# receiverNode_Uno.net
KiCad netlist of a schematic drawn in EAGLE
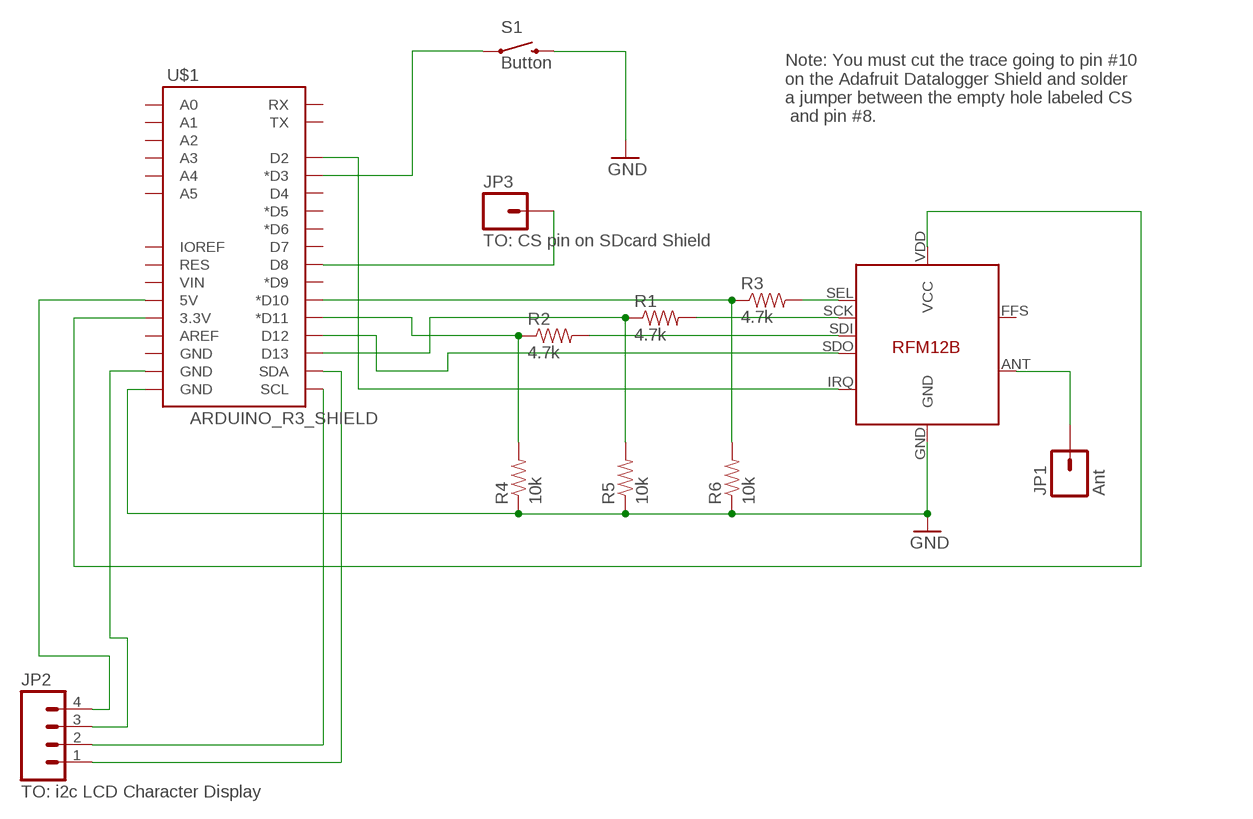
[diagram p0: schematic, sheet 1]

(export (version "E")
  (design (tool "Eeschema 10.0.6"))
  (components
    (comp (ref "JP1")
      (value "Ant")
      (footprint "eagle-import:1X01_LONGPAD")
      (libsource (lib "eagle-import") (part "M01PTH_LONGPAD"))
    )
    (comp (ref "JP2")
      (value "TO: i2c LCD Character Display")
      (footprint "eagle-import:1X04_LONGPADS")
      (libsource (lib "eagle-import") (part "M04LONGPADS"))
    )
    (comp (ref "JP3")
      (value "TO: CS pin on SDcard Shield")
      (footprint "eagle-import:1X01_LONGPAD")
      (libsource (lib "eagle-import") (part "M01PTH_LONGPAD"))
    )
    (comp (ref "R1")
      (value "4.7k")
      (footprint "eagle-import:AXIAL-0.3")
      (libsource (lib "eagle-import") (part "RESISTORAXIAL-0.3"))
    )
    (comp (ref "R2")
      (value "4.7k")
      (footprint "eagle-import:AXIAL-0.3")
      (libsource (lib "eagle-import") (part "RESISTORAXIAL-0.3"))
    )
    (comp (ref "R3")
      (value "4.7k")
      (footprint "eagle-import:AXIAL-0.3")
      (libsource (lib "eagle-import") (part "RESISTORAXIAL-0.3"))
    )
    (comp (ref "R4")
      (value "10k")
      (footprint "eagle-import:AXIAL-0.3")
      (libsource (lib "eagle-import") (part "RESISTORAXIAL-0.3"))
    )
    (comp (ref "R5")
      (value "10k")
      (footprint "eagle-import:AXIAL-0.3")
      (libsource (lib "eagle-import") (part "RESISTORAXIAL-0.3"))
    )
    (comp (ref "R6")
      (value "10k")
      (footprint "eagle-import:AXIAL-0.3")
      (libsource (lib "eagle-import") (part "RESISTORAXIAL-0.3"))
    )
    (comp (ref "S1")
      (value "Button")
      (footprint "eagle-import:TACTILE-PTH")
      (libsource (lib "eagle-import") (part "SWITCH-MOMENTARY-2PTH"))
    )
    (comp (ref "U$1")
      (value "ARDUINO_R3_SHIELD")
      (footprint "eagle-import:UNO_R3_SHIELD")
      (libsource (lib "eagle-import") (part "ARDUINO_R3_SHIELD"))
    )
    (comp (ref "U$2")
      (value "RFM12B")
      (footprint "eagle-import:RFM12B")
      (libsource (lib "eagle-import") (part "RFM12B"))
    )
  )
  (nets
    (net (code "1") (name "GND") (class "Default")
      (node (ref "R4") (pin "P$1") (pinfunction "1_P$1") (pintype "passive"))
      (node (ref "R5") (pin "P$1") (pinfunction "1_P$1") (pintype "passive"))
      (node (ref "R6") (pin "P$1") (pinfunction "1_P$1") (pintype "passive"))
      (node (ref "S1") (pin "3") (pinfunction "2_3") (pintype "passive"))
      (node (ref "U$1") (pin "GND@0") (pinfunction "GND_GND@0") (pintype "bidirectional"))
      (node (ref "U$2") (pin "GND") (pinfunction "GND_GND") (pintype "power_in"))
    )
    (net (code "2") (name "Net-(JP1-Pad1)") (class "Default")
      (node (ref "JP1") (pin "1") (pinfunction "1_1") (pintype "passive"))
      (node (ref "U$2") (pin "ANT") (pinfunction "ANT_ANT") (pintype "passive"))
    )
    (net (code "3") (name "Net-(JP2-Pad1)") (class "Default")
      (node (ref "JP2") (pin "1") (pinfunction "1_1") (pintype "passive"))
      (node (ref "U$1") (pin "SDA") (pinfunction "SDA_SDA") (pintype "bidirectional"))
    )
    (net (code "4") (name "Net-(JP2-Pad2)") (class "Default")
      (node (ref "JP2") (pin "2") (pinfunction "2_2") (pintype "passive"))
      (node (ref "U$1") (pin "SCL") (pinfunction "SCL_SCL") (pintype "bidirectional"))
    )
    (net (code "5") (name "Net-(JP2-Pad3)") (class "Default")
      (node (ref "JP2") (pin "3") (pinfunction "3_3") (pintype "passive"))
      (node (ref "U$1") (pin "GND@1") (pinfunction "GND_GND@1") (pintype "bidirectional"))
    )
    (net (code "6") (name "Net-(JP2-Pad4)") (class "Default")
      (node (ref "JP2") (pin "4") (pinfunction "4_4") (pintype "passive"))
      (node (ref "U$1") (pin "5V") (pinfunction "5V_5V") (pintype "bidirectional"))
    )
    (net (code "7") (name "Net-(JP3-Pad1)") (class "Default")
      (node (ref "JP3") (pin "1") (pinfunction "1_1") (pintype "passive"))
      (node (ref "U$1") (pin "D8") (pinfunction "D8_D8") (pintype "bidirectional"))
    )
    (net (code "8") (name "Net-(R1-1)") (class "Default")
      (node (ref "R1") (pin "P$1") (pinfunction "1_P$1") (pintype "passive"))
      (node (ref "R5") (pin "P$2") (pinfunction "2_P$2") (pintype "passive"))
      (node (ref "U$1") (pin "D13") (pinfunction "D13_D13") (pintype "bidirectional"))
    )
    (net (code "9") (name "Net-(R1-2)") (class "Default")
      (node (ref "R1") (pin "P$2") (pinfunction "2_P$2") (pintype "passive"))
      (node (ref "U$2") (pin "SCK") (pinfunction "SCK_SCK") (pintype "input"))
    )
    (net (code "10") (name "Net-(R2-1)") (class "Default")
      (node (ref "R2") (pin "P$1") (pinfunction "1_P$1") (pintype "passive"))
      (node (ref "R4") (pin "P$2") (pinfunction "2_P$2") (pintype "passive"))
      (node (ref "U$1") (pin "D11") (pinfunction "*D11_D11") (pintype "bidirectional"))
    )
    (net (code "11") (name "Net-(R2-2)") (class "Default")
      (node (ref "R2") (pin "P$2") (pinfunction "2_P$2") (pintype "passive"))
      (node (ref "U$2") (pin "SDI") (pinfunction "SDI_SDI") (pintype "input"))
    )
    (net (code "12") (name "Net-(R3-1)") (class "Default")
      (node (ref "R3") (pin "P$1") (pinfunction "1_P$1") (pintype "passive"))
      (node (ref "R6") (pin "P$2") (pinfunction "2_P$2") (pintype "passive"))
      (node (ref "U$1") (pin "D10") (pinfunction "*D10_D10") (pintype "bidirectional"))
    )
    (net (code "13") (name "Net-(R3-2)") (class "Default")
      (node (ref "R3") (pin "P$2") (pinfunction "2_P$2") (pintype "passive"))
      (node (ref "U$2") (pin "SEL") (pinfunction "SEL_SEL") (pintype "input"))
    )
    (net (code "14") (name "Net-(U$1-*D3)") (class "Default")
      (node (ref "S1") (pin "1") (pinfunction "1_1") (pintype "passive"))
      (node (ref "U$1") (pin "D3") (pinfunction "*D3_D3") (pintype "bidirectional"))
    )
    (net (code "15") (name "Net-(U$1-PadD2)") (class "Default")
      (node (ref "U$1") (pin "D2") (pinfunction "D2_D2") (pintype "bidirectional"))
      (node (ref "U$2") (pin "IRQ") (pinfunction "IRQ_IRQ") (pintype "open_collector"))
    )
    (net (code "16") (name "Net-(U$1-PadD12)") (class "Default")
      (node (ref "U$1") (pin "D12") (pinfunction "D12_D12") (pintype "bidirectional"))
      (node (ref "U$2") (pin "SDO") (pinfunction "SDO_SDO") (pintype "output"))
    )
    (net (code "17") (name "Net-(U$2-VCC)") (class "Default")
      (node (ref "U$1") (pin "3.3V") (pinfunction "3.3V_3.3V") (pintype "bidirectional"))
      (node (ref "U$2") (pin "VDD") (pinfunction "VCC_VDD") (pintype "power_in"))
    )
    (net (code "18") (name "unconnected-(U$1-*D5-PadD5)") (class "Default")
      (node (ref "U$1") (pin "D5") (pinfunction "*D5_D5") (pintype "bidirectional"))
    )
    (net (code "19") (name "unconnected-(U$1-*D6-PadD6)") (class "Default")
      (node (ref "U$1") (pin "D6") (pinfunction "*D6_D6") (pintype "bidirectional"))
    )
    (net (code "20") (name "unconnected-(U$1-*D9-PadD9)") (class "Default")
      (node (ref "U$1") (pin "D9") (pinfunction "*D9_D9") (pintype "bidirectional"))
    )
    (net (code "21") (name "unconnected-(U$1-GND-PadGND@2)") (class "Default")
      (node (ref "U$1") (pin "GND@2") (pinfunction "GND_GND@2") (pintype "bidirectional"))
    )
    (net (code "22") (name "unconnected-(U$1-PadA0)") (class "Default")
      (node (ref "U$1") (pin "A0") (pinfunction "A0_A0") (pintype "bidirectional"))
    )
    (net (code "23") (name "unconnected-(U$1-PadA1)") (class "Default")
      (node (ref "U$1") (pin "A1") (pinfunction "A1_A1") (pintype "bidirectional"))
    )
    (net (code "24") (name "unconnected-(U$1-PadA2)") (class "Default")
      (node (ref "U$1") (pin "A2") (pinfunction "A2_A2") (pintype "bidirectional"))
    )
    (net (code "25") (name "unconnected-(U$1-PadA3)") (class "Default")
      (node (ref "U$1") (pin "A3") (pinfunction "A3_A3") (pintype "bidirectional"))
    )
    (net (code "26") (name "unconnected-(U$1-PadA4)") (class "Default")
      (node (ref "U$1") (pin "A4") (pinfunction "A4_A4") (pintype "bidirectional"))
    )
    (net (code "27") (name "unconnected-(U$1-PadA5)") (class "Default")
      (node (ref "U$1") (pin "A5") (pinfunction "A5_A5") (pintype "bidirectional"))
    )
    (net (code "28") (name "unconnected-(U$1-PadAREF)") (class "Default")
      (node (ref "U$1") (pin "AREF") (pinfunction "AREF_AREF") (pintype "bidirectional"))
    )
    (net (code "29") (name "unconnected-(U$1-PadD4)") (class "Default")
      (node (ref "U$1") (pin "D4") (pinfunction "D4_D4") (pintype "bidirectional"))
    )
    (net (code "30") (name "unconnected-(U$1-PadD7)") (class "Default")
      (node (ref "U$1") (pin "D7") (pinfunction "D7_D7") (pintype "bidirectional"))
    )
    (net (code "31") (name "unconnected-(U$1-PadIOREF)") (class "Default")
      (node (ref "U$1") (pin "IOREF") (pinfunction "IOREF_IOREF") (pintype "bidirectional"))
    )
    (net (code "32") (name "unconnected-(U$1-PadRES)") (class "Default")
      (node (ref "U$1") (pin "RES") (pinfunction "RES_RES") (pintype "bidirectional"))
    )
    (net (code "33") (name "unconnected-(U$1-PadRX)") (class "Default")
      (node (ref "U$1") (pin "RX") (pinfunction "RX_RX") (pintype "bidirectional"))
    )
    (net (code "34") (name "unconnected-(U$1-PadTX)") (class "Default")
      (node (ref "U$1") (pin "TX") (pinfunction "TX_TX") (pintype "bidirectional"))
    )
    (net (code "35") (name "unconnected-(U$1-PadVIN)") (class "Default")
      (node (ref "U$1") (pin "VIN") (pinfunction "VIN_VIN") (pintype "bidirectional"))
    )
    (net (code "36") (name "unconnected-(U$2-PadFFS)") (class "Default")
      (node (ref "U$2") (pin "FFS") (pinfunction "FFS_FFS") (pintype "bidirectional"))
    )
  )
)
